# UPL_KeyBoard.net
KiCad netlist of a schematic drawn in EAGLE
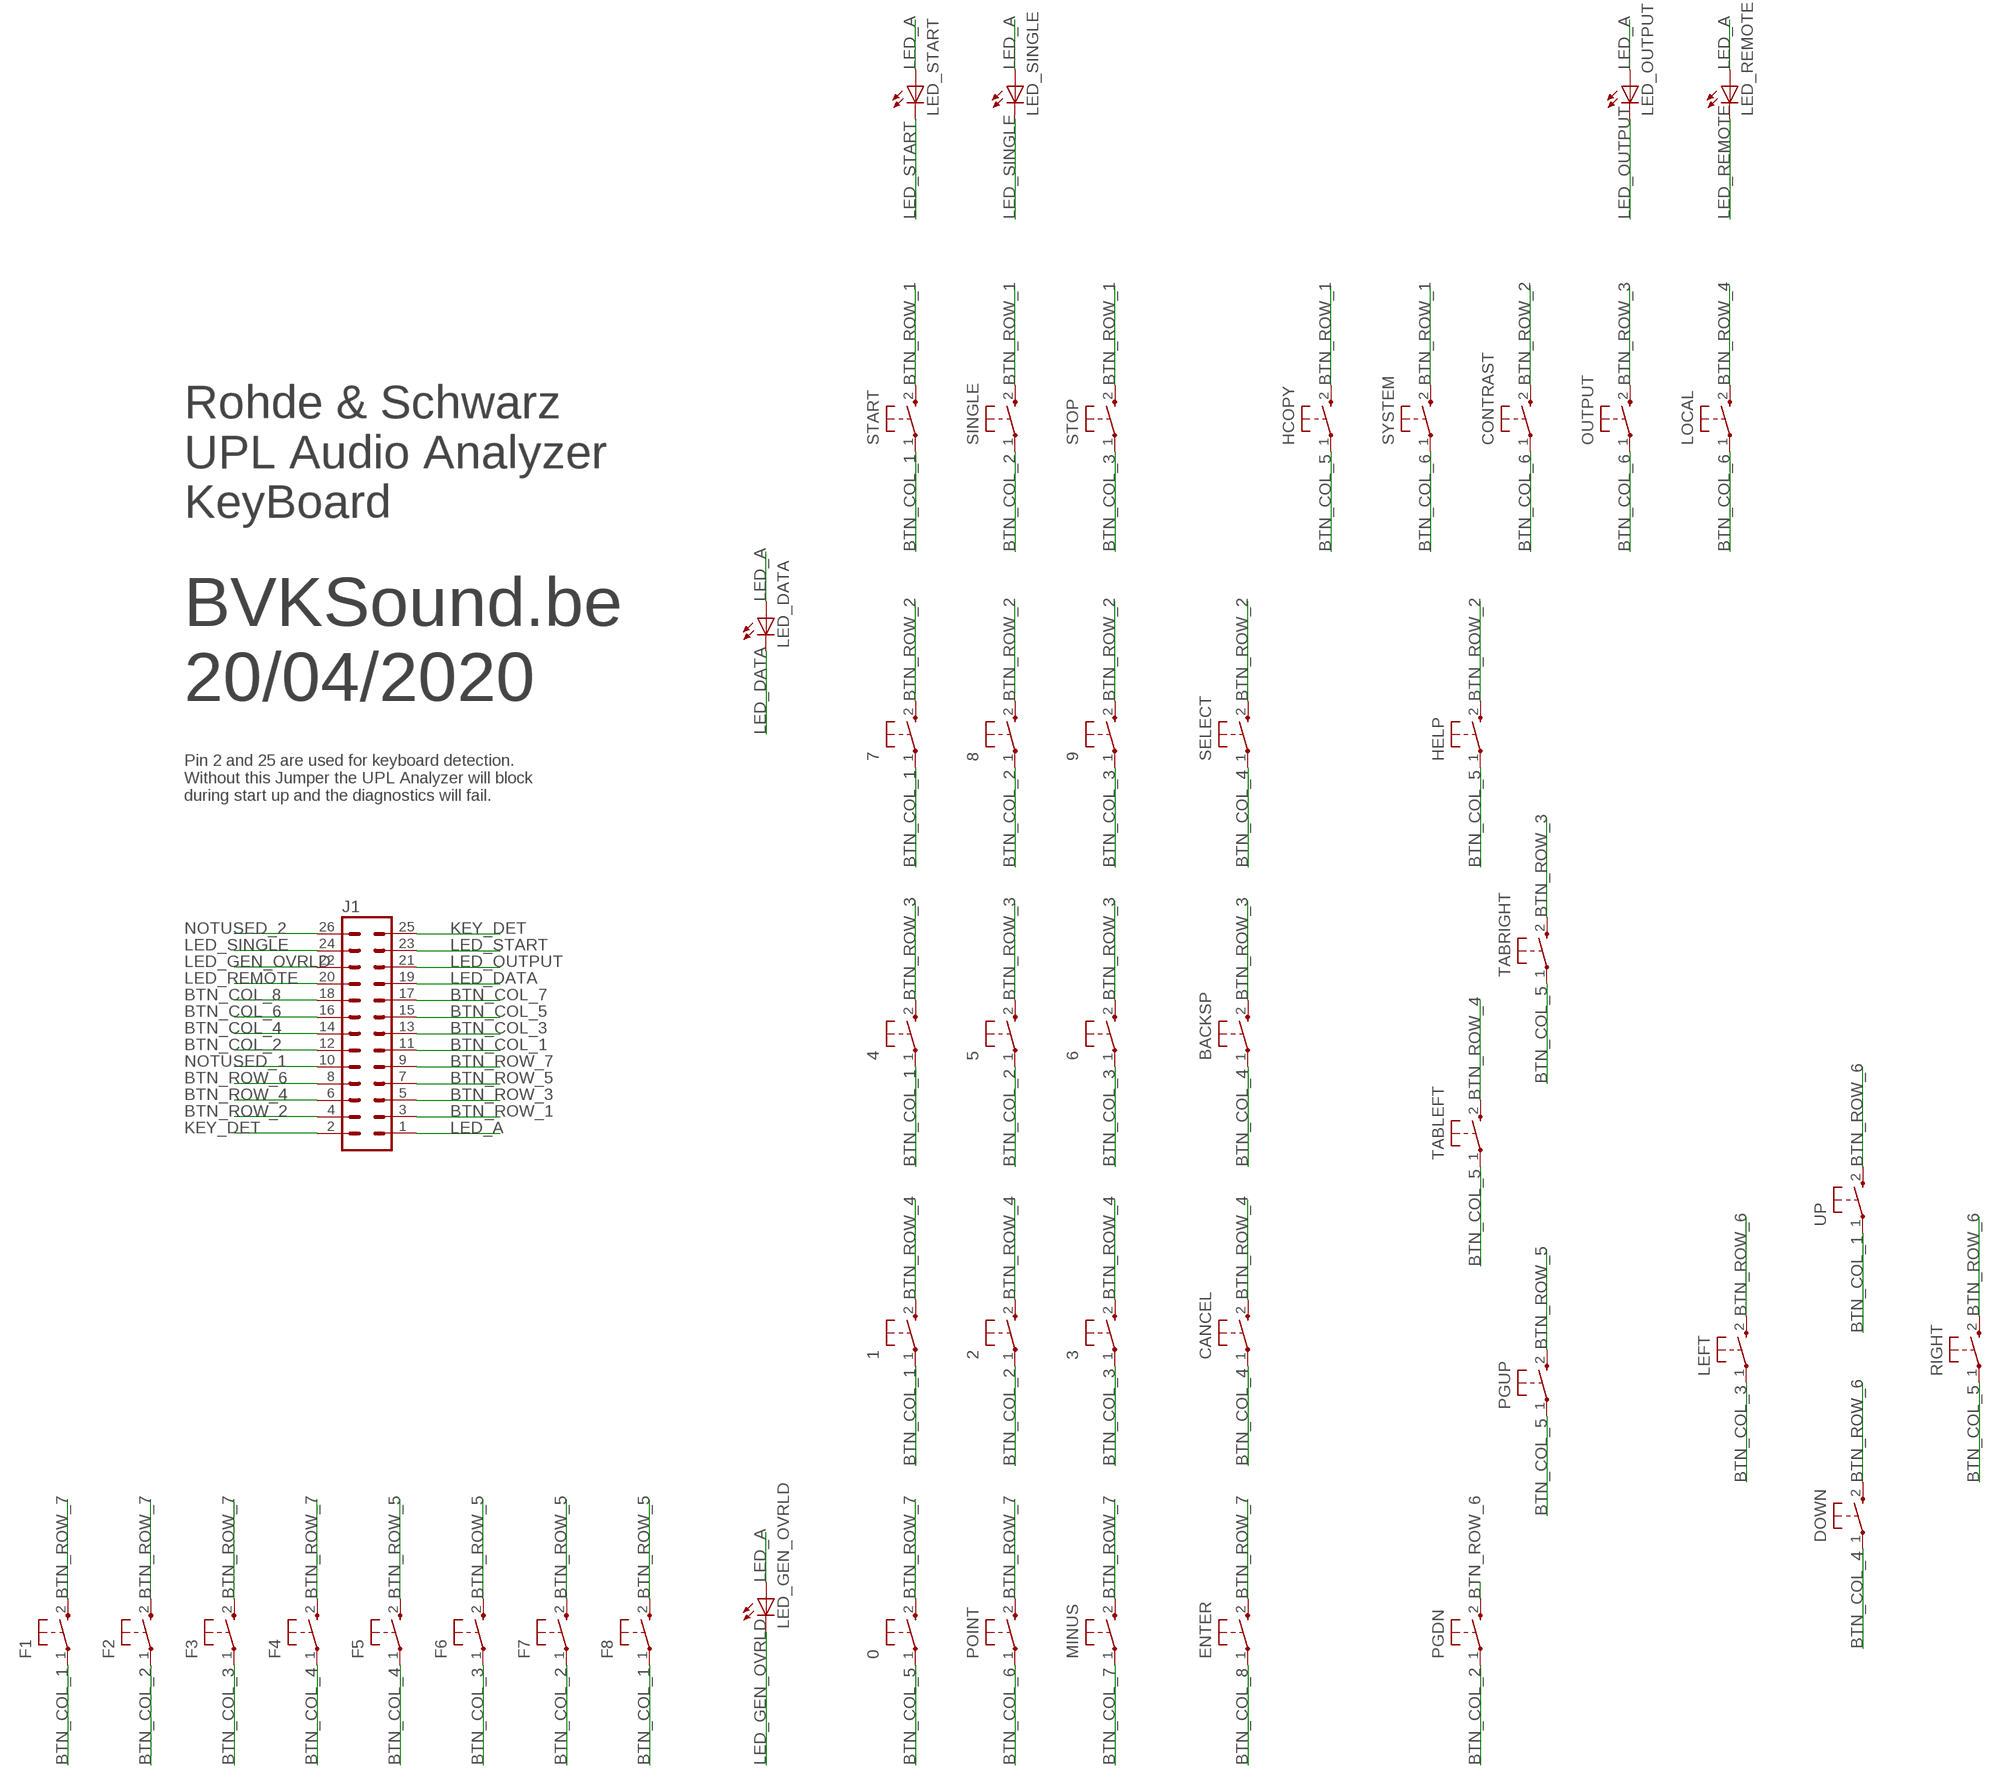
[diagram p0: schematic, sheet 1]

(export (version "E")
  (design (tool "Eeschema 10.0.6"))
  (components
    (comp (ref "0")
      (value "ALPS_SKQYAFE010")
      (footprint "eagle-import:ALPS_SKQYAFE010")
      (libsource (lib "eagle-import") (part "ALPS_SKQYAFE010"))
    )
    (comp (ref "1")
      (value "ALPS_SKQYAFE010")
      (footprint "eagle-import:ALPS_SKQYAFE010")
      (libsource (lib "eagle-import") (part "ALPS_SKQYAFE010"))
    )
    (comp (ref "2")
      (value "ALPS_SKQYAFE010")
      (footprint "eagle-import:ALPS_SKQYAFE010")
      (libsource (lib "eagle-import") (part "ALPS_SKQYAFE010"))
    )
    (comp (ref "3")
      (value "ALPS_SKQYAFE010")
      (footprint "eagle-import:ALPS_SKQYAFE010")
      (libsource (lib "eagle-import") (part "ALPS_SKQYAFE010"))
    )
    (comp (ref "4")
      (value "ALPS_SKQYAFE010")
      (footprint "eagle-import:ALPS_SKQYAFE010")
      (libsource (lib "eagle-import") (part "ALPS_SKQYAFE010"))
    )
    (comp (ref "5")
      (value "ALPS_SKQYAFE010")
      (footprint "eagle-import:ALPS_SKQYAFE010")
      (libsource (lib "eagle-import") (part "ALPS_SKQYAFE010"))
    )
    (comp (ref "6")
      (value "ALPS_SKQYAFE010")
      (footprint "eagle-import:ALPS_SKQYAFE010")
      (libsource (lib "eagle-import") (part "ALPS_SKQYAFE010"))
    )
    (comp (ref "7")
      (value "ALPS_SKQYAFE010")
      (footprint "eagle-import:ALPS_SKQYAFE010")
      (libsource (lib "eagle-import") (part "ALPS_SKQYAFE010"))
    )
    (comp (ref "8")
      (value "ALPS_SKQYAFE010")
      (footprint "eagle-import:ALPS_SKQYAFE010")
      (libsource (lib "eagle-import") (part "ALPS_SKQYAFE010"))
    )
    (comp (ref "9")
      (value "ALPS_SKQYAFE010")
      (footprint "eagle-import:ALPS_SKQYAFE010")
      (libsource (lib "eagle-import") (part "ALPS_SKQYAFE010"))
    )
    (comp (ref "BACKSP")
      (value "ALPS_SKQYAFE010")
      (footprint "eagle-import:ALPS_SKQYAFE010")
      (libsource (lib "eagle-import") (part "ALPS_SKQYAFE010"))
    )
    (comp (ref "CANCEL")
      (value "ALPS_SKQYAFE010")
      (footprint "eagle-import:ALPS_SKQYAFE010")
      (libsource (lib "eagle-import") (part "ALPS_SKQYAFE010"))
    )
    (comp (ref "CONTRAST")
      (value "ALPS_SKQYAFE010")
      (footprint "eagle-import:ALPS_SKQYAFE010")
      (libsource (lib "eagle-import") (part "ALPS_SKQYAFE010"))
    )
    (comp (ref "DOWN")
      (value "ALPS_SKQYAFE010")
      (footprint "eagle-import:ALPS_SKQYAFE010")
      (libsource (lib "eagle-import") (part "ALPS_SKQYAFE010"))
    )
    (comp (ref "ENTER")
      (value "ALPS_SKQYAFE010")
      (footprint "eagle-import:ALPS_SKQYAFE010")
      (libsource (lib "eagle-import") (part "ALPS_SKQYAFE010"))
    )
    (comp (ref "F1")
      (value "ALPS_SKQYAFE010")
      (footprint "eagle-import:ALPS_SKQYAFE010")
      (libsource (lib "eagle-import") (part "ALPS_SKQYAFE010"))
    )
    (comp (ref "F2")
      (value "ALPS_SKQYAFE010")
      (footprint "eagle-import:ALPS_SKQYAFE010")
      (libsource (lib "eagle-import") (part "ALPS_SKQYAFE010"))
    )
    (comp (ref "F3")
      (value "ALPS_SKQYAFE010")
      (footprint "eagle-import:ALPS_SKQYAFE010")
      (libsource (lib "eagle-import") (part "ALPS_SKQYAFE010"))
    )
    (comp (ref "F4")
      (value "ALPS_SKQYAFE010")
      (footprint "eagle-import:ALPS_SKQYAFE010")
      (libsource (lib "eagle-import") (part "ALPS_SKQYAFE010"))
    )
    (comp (ref "F5")
      (value "ALPS_SKQYAFE010")
      (footprint "eagle-import:ALPS_SKQYAFE010")
      (libsource (lib "eagle-import") (part "ALPS_SKQYAFE010"))
    )
    (comp (ref "F6")
      (value "ALPS_SKQYAFE010")
      (footprint "eagle-import:ALPS_SKQYAFE010")
      (libsource (lib "eagle-import") (part "ALPS_SKQYAFE010"))
    )
    (comp (ref "F7")
      (value "ALPS_SKQYAFE010")
      (footprint "eagle-import:ALPS_SKQYAFE010")
      (libsource (lib "eagle-import") (part "ALPS_SKQYAFE010"))
    )
    (comp (ref "F8")
      (value "ALPS_SKQYAFE010")
      (footprint "eagle-import:ALPS_SKQYAFE010")
      (libsource (lib "eagle-import") (part "ALPS_SKQYAFE010"))
    )
    (comp (ref "HCOPY")
      (value "ALPS_SKQYAFE010")
      (footprint "eagle-import:ALPS_SKQYAFE010")
      (libsource (lib "eagle-import") (part "ALPS_SKQYAFE010"))
    )
    (comp (ref "HELP")
      (value "ALPS_SKQYAFE010")
      (footprint "eagle-import:ALPS_SKQYAFE010")
      (libsource (lib "eagle-import") (part "ALPS_SKQYAFE010"))
    )
    (comp (ref "J1")
      (value "ML26")
      (footprint "eagle-import:ML26")
      (libsource (lib "eagle-import") (part "ML26"))
    )
    (comp (ref "LED_DATA")
      (value "LEDCHIPLED_1206")
      (footprint "eagle-import:CHIPLED_1206")
      (libsource (lib "eagle-import") (part "LEDCHIPLED_1206"))
    )
    (comp (ref "LED_GEN_OVRLD")
      (value "LEDCHIPLED_1206")
      (footprint "eagle-import:CHIPLED_1206")
      (libsource (lib "eagle-import") (part "LEDCHIPLED_1206"))
    )
    (comp (ref "LED_OUTPUT")
      (value "LEDCHIPLED_1206")
      (footprint "eagle-import:CHIPLED_1206")
      (libsource (lib "eagle-import") (part "LEDCHIPLED_1206"))
    )
    (comp (ref "LED_REMOTE")
      (value "LEDCHIPLED_1206")
      (footprint "eagle-import:CHIPLED_1206")
      (libsource (lib "eagle-import") (part "LEDCHIPLED_1206"))
    )
    (comp (ref "LED_SINGLE")
      (value "LEDCHIPLED_1206")
      (footprint "eagle-import:CHIPLED_1206")
      (libsource (lib "eagle-import") (part "LEDCHIPLED_1206"))
    )
    (comp (ref "LED_START")
      (value "LEDCHIPLED_1206")
      (footprint "eagle-import:CHIPLED_1206")
      (libsource (lib "eagle-import") (part "LEDCHIPLED_1206"))
    )
    (comp (ref "LEFT")
      (value "ALPS_SKQYAFE010")
      (footprint "eagle-import:ALPS_SKQYAFE010")
      (libsource (lib "eagle-import") (part "ALPS_SKQYAFE010"))
    )
    (comp (ref "LOCAL")
      (value "ALPS_SKQYAFE010")
      (footprint "eagle-import:ALPS_SKQYAFE010")
      (libsource (lib "eagle-import") (part "ALPS_SKQYAFE010"))
    )
    (comp (ref "MINUS")
      (value "ALPS_SKQYAFE010")
      (footprint "eagle-import:ALPS_SKQYAFE010")
      (libsource (lib "eagle-import") (part "ALPS_SKQYAFE010"))
    )
    (comp (ref "OUTPUT")
      (value "ALPS_SKQYAFE010")
      (footprint "eagle-import:ALPS_SKQYAFE010")
      (libsource (lib "eagle-import") (part "ALPS_SKQYAFE010"))
    )
    (comp (ref "PGDN")
      (value "ALPS_SKQYAFE010")
      (footprint "eagle-import:ALPS_SKQYAFE010")
      (libsource (lib "eagle-import") (part "ALPS_SKQYAFE010"))
    )
    (comp (ref "PGUP")
      (value "ALPS_SKQYAFE010")
      (footprint "eagle-import:ALPS_SKQYAFE010")
      (libsource (lib "eagle-import") (part "ALPS_SKQYAFE010"))
    )
    (comp (ref "POINT")
      (value "ALPS_SKQYAFE010")
      (footprint "eagle-import:ALPS_SKQYAFE010")
      (libsource (lib "eagle-import") (part "ALPS_SKQYAFE010"))
    )
    (comp (ref "RIGHT")
      (value "ALPS_SKQYAFE010")
      (footprint "eagle-import:ALPS_SKQYAFE010")
      (libsource (lib "eagle-import") (part "ALPS_SKQYAFE010"))
    )
    (comp (ref "SELECT")
      (value "ALPS_SKQYAFE010")
      (footprint "eagle-import:ALPS_SKQYAFE010")
      (libsource (lib "eagle-import") (part "ALPS_SKQYAFE010"))
    )
    (comp (ref "SINGLE")
      (value "ALPS_SKQYAFE010")
      (footprint "eagle-import:ALPS_SKQYAFE010")
      (libsource (lib "eagle-import") (part "ALPS_SKQYAFE010"))
    )
    (comp (ref "START")
      (value "ALPS_SKQYAFE010")
      (footprint "eagle-import:ALPS_SKQYAFE010")
      (libsource (lib "eagle-import") (part "ALPS_SKQYAFE010"))
    )
    (comp (ref "STOP")
      (value "ALPS_SKQYAFE010")
      (footprint "eagle-import:ALPS_SKQYAFE010")
      (libsource (lib "eagle-import") (part "ALPS_SKQYAFE010"))
    )
    (comp (ref "SYSTEM")
      (value "ALPS_SKQYAFE010")
      (footprint "eagle-import:ALPS_SKQYAFE010")
      (libsource (lib "eagle-import") (part "ALPS_SKQYAFE010"))
    )
    (comp (ref "TABLEFT")
      (value "ALPS_SKQYAFE010")
      (footprint "eagle-import:ALPS_SKQYAFE010")
      (libsource (lib "eagle-import") (part "ALPS_SKQYAFE010"))
    )
    (comp (ref "TABRIGHT")
      (value "ALPS_SKQYAFE010")
      (footprint "eagle-import:ALPS_SKQYAFE010")
      (libsource (lib "eagle-import") (part "ALPS_SKQYAFE010"))
    )
    (comp (ref "UP")
      (value "ALPS_SKQYAFE010")
      (footprint "eagle-import:ALPS_SKQYAFE010")
      (libsource (lib "eagle-import") (part "ALPS_SKQYAFE010"))
    )
  )
  (nets
    (net (code "1") (name "/BTN_COL_1") (class "Default")
      (node (ref "1") (pin "1") (pinfunction "1_1") (pintype "passive"))
      (node (ref "4") (pin "1") (pinfunction "1_1") (pintype "passive"))
      (node (ref "7") (pin "1") (pinfunction "1_1") (pintype "passive"))
      (node (ref "F1") (pin "1") (pinfunction "1_1") (pintype "passive"))
      (node (ref "F8") (pin "1") (pinfunction "1_1") (pintype "passive"))
      (node (ref "J1") (pin "11") (pinfunction "11_11") (pintype "passive"))
      (node (ref "START") (pin "1") (pinfunction "1_1") (pintype "passive"))
      (node (ref "UP") (pin "1") (pinfunction "1_1") (pintype "passive"))
    )
    (net (code "2") (name "/BTN_COL_2") (class "Default")
      (node (ref "2") (pin "1") (pinfunction "1_1") (pintype "passive"))
      (node (ref "5") (pin "1") (pinfunction "1_1") (pintype "passive"))
      (node (ref "8") (pin "1") (pinfunction "1_1") (pintype "passive"))
      (node (ref "F2") (pin "1") (pinfunction "1_1") (pintype "passive"))
      (node (ref "F7") (pin "1") (pinfunction "1_1") (pintype "passive"))
      (node (ref "J1") (pin "12") (pinfunction "12_12") (pintype "passive"))
      (node (ref "PGDN") (pin "1") (pinfunction "1_1") (pintype "passive"))
      (node (ref "SINGLE") (pin "1") (pinfunction "1_1") (pintype "passive"))
    )
    (net (code "3") (name "/BTN_COL_3") (class "Default")
      (node (ref "3") (pin "1") (pinfunction "1_1") (pintype "passive"))
      (node (ref "6") (pin "1") (pinfunction "1_1") (pintype "passive"))
      (node (ref "9") (pin "1") (pinfunction "1_1") (pintype "passive"))
      (node (ref "F3") (pin "1") (pinfunction "1_1") (pintype "passive"))
      (node (ref "F6") (pin "1") (pinfunction "1_1") (pintype "passive"))
      (node (ref "J1") (pin "13") (pinfunction "13_13") (pintype "passive"))
      (node (ref "LEFT") (pin "1") (pinfunction "1_1") (pintype "passive"))
      (node (ref "STOP") (pin "1") (pinfunction "1_1") (pintype "passive"))
    )
    (net (code "4") (name "/BTN_COL_4") (class "Default")
      (node (ref "BACKSP") (pin "1") (pinfunction "1_1") (pintype "passive"))
      (node (ref "CANCEL") (pin "1") (pinfunction "1_1") (pintype "passive"))
      (node (ref "DOWN") (pin "1") (pinfunction "1_1") (pintype "passive"))
      (node (ref "F4") (pin "1") (pinfunction "1_1") (pintype "passive"))
      (node (ref "F5") (pin "1") (pinfunction "1_1") (pintype "passive"))
      (node (ref "J1") (pin "14") (pinfunction "14_14") (pintype "passive"))
      (node (ref "SELECT") (pin "1") (pinfunction "1_1") (pintype "passive"))
    )
    (net (code "5") (name "/BTN_COL_5") (class "Default")
      (node (ref "0") (pin "1") (pinfunction "1_1") (pintype "passive"))
      (node (ref "HCOPY") (pin "1") (pinfunction "1_1") (pintype "passive"))
      (node (ref "HELP") (pin "1") (pinfunction "1_1") (pintype "passive"))
      (node (ref "J1") (pin "15") (pinfunction "15_15") (pintype "passive"))
      (node (ref "PGUP") (pin "1") (pinfunction "1_1") (pintype "passive"))
      (node (ref "RIGHT") (pin "1") (pinfunction "1_1") (pintype "passive"))
      (node (ref "TABLEFT") (pin "1") (pinfunction "1_1") (pintype "passive"))
      (node (ref "TABRIGHT") (pin "1") (pinfunction "1_1") (pintype "passive"))
    )
    (net (code "6") (name "/BTN_COL_6") (class "Default")
      (node (ref "CONTRAST") (pin "1") (pinfunction "1_1") (pintype "passive"))
      (node (ref "J1") (pin "16") (pinfunction "16_16") (pintype "passive"))
      (node (ref "LOCAL") (pin "1") (pinfunction "1_1") (pintype "passive"))
      (node (ref "OUTPUT") (pin "1") (pinfunction "1_1") (pintype "passive"))
      (node (ref "POINT") (pin "1") (pinfunction "1_1") (pintype "passive"))
      (node (ref "SYSTEM") (pin "1") (pinfunction "1_1") (pintype "passive"))
    )
    (net (code "7") (name "/BTN_COL_7") (class "Default")
      (node (ref "J1") (pin "17") (pinfunction "17_17") (pintype "passive"))
      (node (ref "MINUS") (pin "1") (pinfunction "1_1") (pintype "passive"))
    )
    (net (code "8") (name "/BTN_COL_8") (class "Default")
      (node (ref "ENTER") (pin "1") (pinfunction "1_1") (pintype "passive"))
      (node (ref "J1") (pin "18") (pinfunction "18_18") (pintype "passive"))
    )
    (net (code "9") (name "/BTN_ROW_1") (class "Default")
      (node (ref "HCOPY") (pin "2") (pinfunction "3_2") (pintype "passive"))
      (node (ref "J1") (pin "3") (pinfunction "3_3") (pintype "passive"))
      (node (ref "SINGLE") (pin "2") (pinfunction "3_2") (pintype "passive"))
      (node (ref "START") (pin "2") (pinfunction "3_2") (pintype "passive"))
      (node (ref "STOP") (pin "2") (pinfunction "3_2") (pintype "passive"))
      (node (ref "SYSTEM") (pin "2") (pinfunction "3_2") (pintype "passive"))
    )
    (net (code "10") (name "/BTN_ROW_2") (class "Default")
      (node (ref "7") (pin "2") (pinfunction "3_2") (pintype "passive"))
      (node (ref "8") (pin "2") (pinfunction "3_2") (pintype "passive"))
      (node (ref "9") (pin "2") (pinfunction "3_2") (pintype "passive"))
      (node (ref "CONTRAST") (pin "2") (pinfunction "3_2") (pintype "passive"))
      (node (ref "HELP") (pin "2") (pinfunction "3_2") (pintype "passive"))
      (node (ref "J1") (pin "4") (pinfunction "4_4") (pintype "passive"))
      (node (ref "SELECT") (pin "2") (pinfunction "3_2") (pintype "passive"))
    )
    (net (code "11") (name "/BTN_ROW_3") (class "Default")
      (node (ref "4") (pin "2") (pinfunction "3_2") (pintype "passive"))
      (node (ref "5") (pin "2") (pinfunction "3_2") (pintype "passive"))
      (node (ref "6") (pin "2") (pinfunction "3_2") (pintype "passive"))
      (node (ref "BACKSP") (pin "2") (pinfunction "3_2") (pintype "passive"))
      (node (ref "J1") (pin "5") (pinfunction "5_5") (pintype "passive"))
      (node (ref "OUTPUT") (pin "2") (pinfunction "3_2") (pintype "passive"))
      (node (ref "TABRIGHT") (pin "2") (pinfunction "3_2") (pintype "passive"))
    )
    (net (code "12") (name "/BTN_ROW_4") (class "Default")
      (node (ref "1") (pin "2") (pinfunction "3_2") (pintype "passive"))
      (node (ref "2") (pin "2") (pinfunction "3_2") (pintype "passive"))
      (node (ref "3") (pin "2") (pinfunction "3_2") (pintype "passive"))
      (node (ref "CANCEL") (pin "2") (pinfunction "3_2") (pintype "passive"))
      (node (ref "J1") (pin "6") (pinfunction "6_6") (pintype "passive"))
      (node (ref "LOCAL") (pin "2") (pinfunction "3_2") (pintype "passive"))
      (node (ref "TABLEFT") (pin "2") (pinfunction "3_2") (pintype "passive"))
    )
    (net (code "13") (name "/BTN_ROW_5") (class "Default")
      (node (ref "F5") (pin "2") (pinfunction "3_2") (pintype "passive"))
      (node (ref "F6") (pin "2") (pinfunction "3_2") (pintype "passive"))
      (node (ref "F7") (pin "2") (pinfunction "3_2") (pintype "passive"))
      (node (ref "F8") (pin "2") (pinfunction "3_2") (pintype "passive"))
      (node (ref "J1") (pin "7") (pinfunction "7_7") (pintype "passive"))
      (node (ref "PGUP") (pin "2") (pinfunction "3_2") (pintype "passive"))
    )
    (net (code "14") (name "/BTN_ROW_6") (class "Default")
      (node (ref "DOWN") (pin "2") (pinfunction "3_2") (pintype "passive"))
      (node (ref "J1") (pin "8") (pinfunction "8_8") (pintype "passive"))
      (node (ref "LEFT") (pin "2") (pinfunction "3_2") (pintype "passive"))
      (node (ref "PGDN") (pin "2") (pinfunction "3_2") (pintype "passive"))
      (node (ref "RIGHT") (pin "2") (pinfunction "3_2") (pintype "passive"))
      (node (ref "UP") (pin "2") (pinfunction "3_2") (pintype "passive"))
    )
    (net (code "15") (name "/BTN_ROW_7") (class "Default")
      (node (ref "0") (pin "2") (pinfunction "3_2") (pintype "passive"))
      (node (ref "ENTER") (pin "2") (pinfunction "3_2") (pintype "passive"))
      (node (ref "F1") (pin "2") (pinfunction "3_2") (pintype "passive"))
      (node (ref "F2") (pin "2") (pinfunction "3_2") (pintype "passive"))
      (node (ref "F3") (pin "2") (pinfunction "3_2") (pintype "passive"))
      (node (ref "F4") (pin "2") (pinfunction "3_2") (pintype "passive"))
      (node (ref "J1") (pin "9") (pinfunction "9_9") (pintype "passive"))
      (node (ref "MINUS") (pin "2") (pinfunction "3_2") (pintype "passive"))
      (node (ref "POINT") (pin "2") (pinfunction "3_2") (pintype "passive"))
    )
    (net (code "16") (name "/KEY_DET") (class "Default")
      (node (ref "J1") (pin "2") (pinfunction "2_2") (pintype "passive"))
      (node (ref "J1") (pin "25") (pinfunction "25_25") (pintype "passive"))
    )
    (net (code "17") (name "/LED_A") (class "Default")
      (node (ref "J1") (pin "1") (pinfunction "1_1") (pintype "passive"))
      (node (ref "LED_DATA") (pin "A") (pinfunction "A_A") (pintype "passive"))
      (node (ref "LED_GEN_OVRLD") (pin "A") (pinfunction "A_A") (pintype "passive"))
      (node (ref "LED_OUTPUT") (pin "A") (pinfunction "A_A") (pintype "passive"))
      (node (ref "LED_REMOTE") (pin "A") (pinfunction "A_A") (pintype "passive"))
      (node (ref "LED_SINGLE") (pin "A") (pinfunction "A_A") (pintype "passive"))
      (node (ref "LED_START") (pin "A") (pinfunction "A_A") (pintype "passive"))
    )
    (net (code "18") (name "/LED_DATA") (class "Default")
      (node (ref "J1") (pin "19") (pinfunction "19_19") (pintype "passive"))
      (node (ref "LED_DATA") (pin "C") (pinfunction "C_C") (pintype "passive"))
    )
    (net (code "19") (name "/LED_GEN_OVRLD") (class "Default")
      (node (ref "J1") (pin "22") (pinfunction "22_22") (pintype "passive"))
      (node (ref "LED_GEN_OVRLD") (pin "C") (pinfunction "C_C") (pintype "passive"))
    )
    (net (code "20") (name "/LED_OUTPUT") (class "Default")
      (node (ref "J1") (pin "21") (pinfunction "21_21") (pintype "passive"))
      (node (ref "LED_OUTPUT") (pin "C") (pinfunction "C_C") (pintype "passive"))
    )
    (net (code "21") (name "/LED_REMOTE") (class "Default")
      (node (ref "J1") (pin "20") (pinfunction "20_20") (pintype "passive"))
      (node (ref "LED_REMOTE") (pin "C") (pinfunction "C_C") (pintype "passive"))
    )
    (net (code "22") (name "/LED_SINGLE") (class "Default")
      (node (ref "J1") (pin "24") (pinfunction "24_24") (pintype "passive"))
      (node (ref "LED_SINGLE") (pin "C") (pinfunction "C_C") (pintype "passive"))
    )
    (net (code "23") (name "/LED_START") (class "Default")
      (node (ref "J1") (pin "23") (pinfunction "23_23") (pintype "passive"))
      (node (ref "LED_START") (pin "C") (pinfunction "C_C") (pintype "passive"))
    )
    (net (code "24") (name "/NOTUSED_1") (class "Default")
      (node (ref "J1") (pin "10") (pinfunction "10_10") (pintype "passive"))
    )
    (net (code "25") (name "/NOTUSED_2") (class "Default")
      (node (ref "J1") (pin "26") (pinfunction "26_26") (pintype "passive"))
    )
  )
)
